# MeasureCurrent.net
KiCad netlist of a schematic drawn in EAGLE
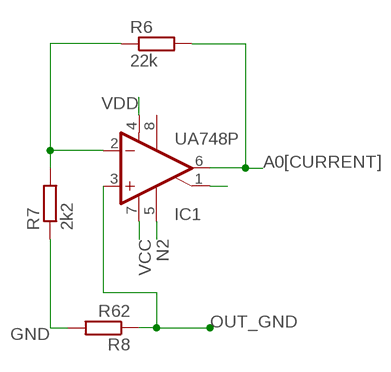
[diagram p0: schematic, sheet 1]

(export (version "E")
  (design (tool "Eeschema 10.0.6"))
  (components
    (comp (ref "IC1")
      (value "UA748P")
      (footprint "eagle-import:DIL08")
      (libsource (lib "eagle-import") (part "748PUA"))
    )
    (comp (ref "R6")
      (value "22k")
      (footprint "eagle-import:0207_12")
      (libsource (lib "eagle-import") (part "R-EU_0207/12"))
    )
    (comp (ref "R7")
      (value "2k2")
      (footprint "eagle-import:0207_12")
      (libsource (lib "eagle-import") (part "R-EU_0207/12"))
    )
    (comp (ref "R8")
      (value "R62")
      (footprint "eagle-import:0207_15")
      (libsource (lib "eagle-import") (part "R-EU_0207/15"))
    )
  )
  (nets
    (net (code "1") (name "/A0[CURRENT]") (class "Default")
      (node (ref "IC1") (pin "6") (pinfunction "OUT_6") (pintype "output"))
      (node (ref "R6") (pin "2") (pinfunction "2_2") (pintype "passive"))
    )
    (net (code "2") (name "/GND") (class "Default")
      (node (ref "R7") (pin "1") (pinfunction "1_1") (pintype "passive"))
      (node (ref "R8") (pin "2") (pinfunction "2_2") (pintype "passive"))
    )
    (net (code "3") (name "/N2") (class "Default")
      (node (ref "IC1") (pin "5") (pinfunction "ON_5") (pintype "passive"))
    )
    (net (code "4") (name "/OUT_GND") (class "Default")
      (node (ref "IC1") (pin "3") (pinfunction "+IN_3") (pintype "input"))
      (node (ref "R8") (pin "1") (pinfunction "1_1") (pintype "passive"))
    )
    (net (code "5") (name "/VCC") (class "Default")
      (node (ref "IC1") (pin "7") (pinfunction "V+_7") (pintype "power_in"))
    )
    (net (code "6") (name "/VDD") (class "Default")
      (node (ref "IC1") (pin "4") (pinfunction "V-_4") (pintype "power_in"))
    )
    (net (code "7") (name "Net-(IC1--IN)") (class "Default")
      (node (ref "IC1") (pin "2") (pinfunction "-IN_2") (pintype "input"))
      (node (ref "R6") (pin "1") (pinfunction "1_1") (pintype "passive"))
      (node (ref "R7") (pin "2") (pinfunction "2_2") (pintype "passive"))
    )
    (net (code "8") (name "unconnected-(IC1-CMP-Pad8)") (class "Default")
      (node (ref "IC1") (pin "8") (pinfunction "CMP_8") (pintype "passive"))
    )
    (net (code "9") (name "unconnected-(IC1-ON{slash}CMP-Pad1)") (class "Default")
      (node (ref "IC1") (pin "1") (pinfunction "ON/CMP_1") (pintype "passive"))
    )
  )
)
